# 007_Ethernet.net
KiCad netlist of a schematic drawn in Altium Designer
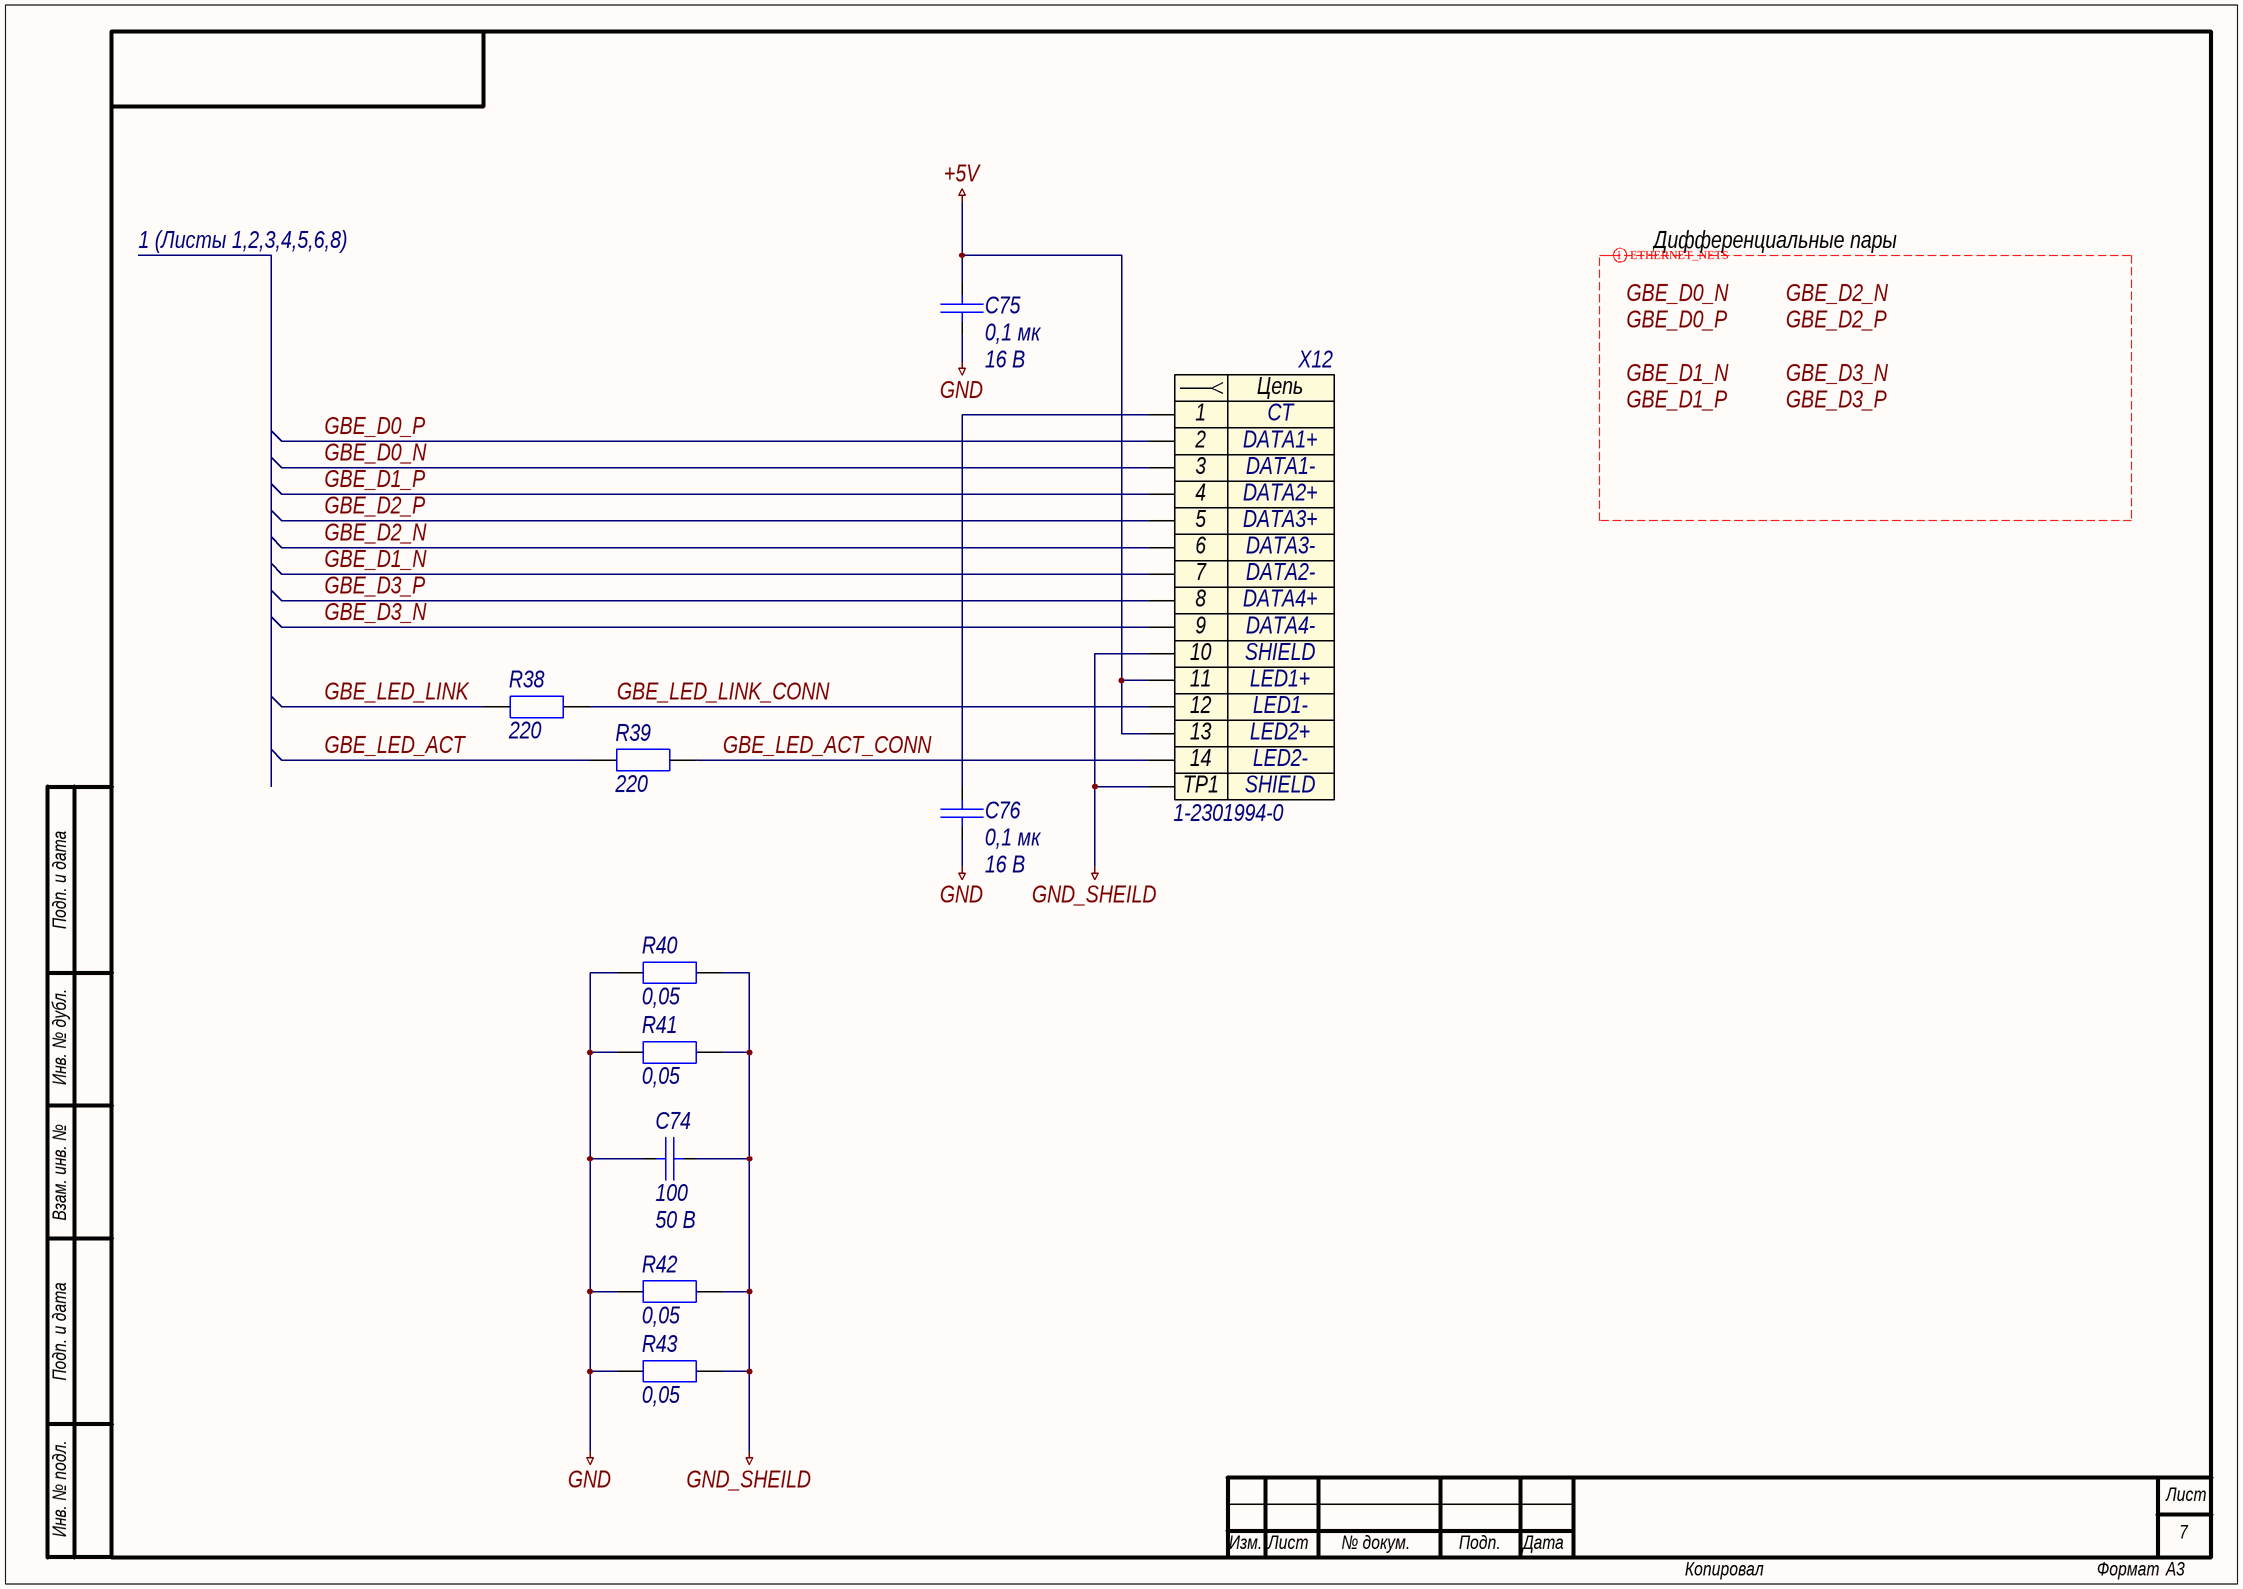
[diagram p0: 007_Ethernet.SchDoc]

(export (version "E")
  (design (tool "Eeschema 10.0.6"))
  (components
    (comp (ref "C74")
      (value "100")
      (footprint "C0402")
      (description "=Описание")
      (fields (field (name "НАПРЯЖЕНИЕ") "50 В"))
      (libsource (lib "Database_Students") (part "CAPACITOR-NONPOLAR"))
    )
    (comp (ref "C75")
      (value "0,1 мк")
      (footprint "C0603")
      (description "=Описание")
      (fields (field (name "НАПРЯЖЕНИЕ") "16 В"))
      (libsource (lib "Database_Students") (part "CAPACITOR-NONPOLAR"))
    )
    (comp (ref "C76")
      (value "0,1 мк")
      (footprint "C0603")
      (description "=Описание")
      (fields (field (name "НАПРЯЖЕНИЕ") "16 В"))
      (libsource (lib "Database_Students") (part "CAPACITOR-NONPOLAR"))
    )
    (comp (ref "R38")
      (value "220")
      (footprint "R0603")
      (description "=Описание")
      (libsource (lib "Database_Students") (part "RESISTOR-COMMON"))
    )
    (comp (ref "R39")
      (value "220")
      (footprint "R0603")
      (description "=Описание")
      (libsource (lib "Database_Students") (part "RESISTOR-COMMON"))
    )
    (comp (ref "R40")
      (value "0,05")
      (footprint "R0603")
      (description "=Описание")
      (libsource (lib "Database_Students") (part "RESISTOR-COMMON"))
    )
    (comp (ref "R41")
      (value "0,05")
      (footprint "R0603")
      (description "=Описание")
      (libsource (lib "Database_Students") (part "RESISTOR-COMMON"))
    )
    (comp (ref "R42")
      (value "0,05")
      (footprint "R0603")
      (description "=Описание")
      (libsource (lib "Database_Students") (part "RESISTOR-COMMON"))
    )
    (comp (ref "R43")
      (value "0,05")
      (footprint "R0603")
      (description "=Описание")
      (libsource (lib "Database_Students") (part "RESISTOR-COMMON"))
    )
    (comp (ref "X12")
      (value "1-2301994-0")
      (footprint "1-2301994-0")
      (description "=Описание")
      (libsource (lib "Database_Students") (part "HEADER-14-TP1-SCT"))
    )
  )
  (nets
    (net (code "1") (name "+5V") (class "Default")
      (node (ref "C75") (pin "1") (pinfunction "1_1") (pintype "passive"))
      (node (ref "X12") (pin "11") (pinfunction "11_11") (pintype "passive"))
      (node (ref "X12") (pin "13") (pinfunction "13_13") (pintype "passive"))
    )
    (net (code "2") (name "/GBE_D0_N") (class "Default")
      (node (ref "X12") (pin "3") (pinfunction "3_3") (pintype "passive"))
    )
    (net (code "3") (name "/GBE_D0_P") (class "Default")
      (node (ref "X12") (pin "2") (pinfunction "2_2") (pintype "passive"))
    )
    (net (code "4") (name "/GBE_D1_N") (class "Default")
      (node (ref "X12") (pin "7") (pinfunction "7_7") (pintype "passive"))
    )
    (net (code "5") (name "/GBE_D1_P") (class "Default")
      (node (ref "X12") (pin "4") (pinfunction "4_4") (pintype "passive"))
    )
    (net (code "6") (name "/GBE_D2_N") (class "Default")
      (node (ref "X12") (pin "6") (pinfunction "6_6") (pintype "passive"))
    )
    (net (code "7") (name "/GBE_D2_P") (class "Default")
      (node (ref "X12") (pin "5") (pinfunction "5_5") (pintype "passive"))
    )
    (net (code "8") (name "/GBE_D3_N") (class "Default")
      (node (ref "X12") (pin "9") (pinfunction "9_9") (pintype "passive"))
    )
    (net (code "9") (name "/GBE_D3_P") (class "Default")
      (node (ref "X12") (pin "8") (pinfunction "8_8") (pintype "passive"))
    )
    (net (code "10") (name "/GBE_LED_ACT") (class "Default")
      (node (ref "R39") (pin "1") (pinfunction "1_1") (pintype "passive"))
    )
    (net (code "11") (name "/GBE_LED_ACT_CONN") (class "Default")
      (node (ref "R39") (pin "2") (pinfunction "2_2") (pintype "passive"))
      (node (ref "X12") (pin "14") (pinfunction "14_14") (pintype "passive"))
    )
    (net (code "12") (name "/GBE_LED_LINK") (class "Default")
      (node (ref "R38") (pin "1") (pinfunction "1_1") (pintype "passive"))
    )
    (net (code "13") (name "/GBE_LED_LINK_CONN") (class "Default")
      (node (ref "R38") (pin "2") (pinfunction "2_2") (pintype "passive"))
      (node (ref "X12") (pin "12") (pinfunction "12_12") (pintype "passive"))
    )
    (net (code "14") (name "GND") (class "Default")
      (node (ref "C74") (pin "2") (pinfunction "2_2") (pintype "passive"))
      (node (ref "C75") (pin "2") (pinfunction "2_2") (pintype "passive"))
      (node (ref "C76") (pin "2") (pinfunction "2_2") (pintype "passive"))
      (node (ref "R40") (pin "1") (pinfunction "1_1") (pintype "passive"))
      (node (ref "R41") (pin "1") (pinfunction "1_1") (pintype "passive"))
      (node (ref "R42") (pin "1") (pinfunction "1_1") (pintype "passive"))
      (node (ref "R43") (pin "1") (pinfunction "1_1") (pintype "passive"))
    )
    (net (code "15") (name "GND_SHEILD") (class "Default")
      (node (ref "C74") (pin "1") (pinfunction "1_1") (pintype "passive"))
      (node (ref "R40") (pin "2") (pinfunction "2_2") (pintype "passive"))
      (node (ref "R41") (pin "2") (pinfunction "2_2") (pintype "passive"))
      (node (ref "R42") (pin "2") (pinfunction "2_2") (pintype "passive"))
      (node (ref "R43") (pin "2") (pinfunction "2_2") (pintype "passive"))
      (node (ref "X12") (pin "10") (pinfunction "10_10") (pintype "passive"))
      (node (ref "X12") (pin "TP1") (pinfunction "TP1_TP1") (pintype "passive"))
    )
    (net (code "16") (name "Net-(C76-Pad1)") (class "Default")
      (node (ref "C76") (pin "1") (pinfunction "1_1") (pintype "passive"))
      (node (ref "X12") (pin "1") (pinfunction "1_1") (pintype "passive"))
    )
  )
)
